# CECILIA_00.net
KiCad netlist of a schematic drawn in Altium Designer
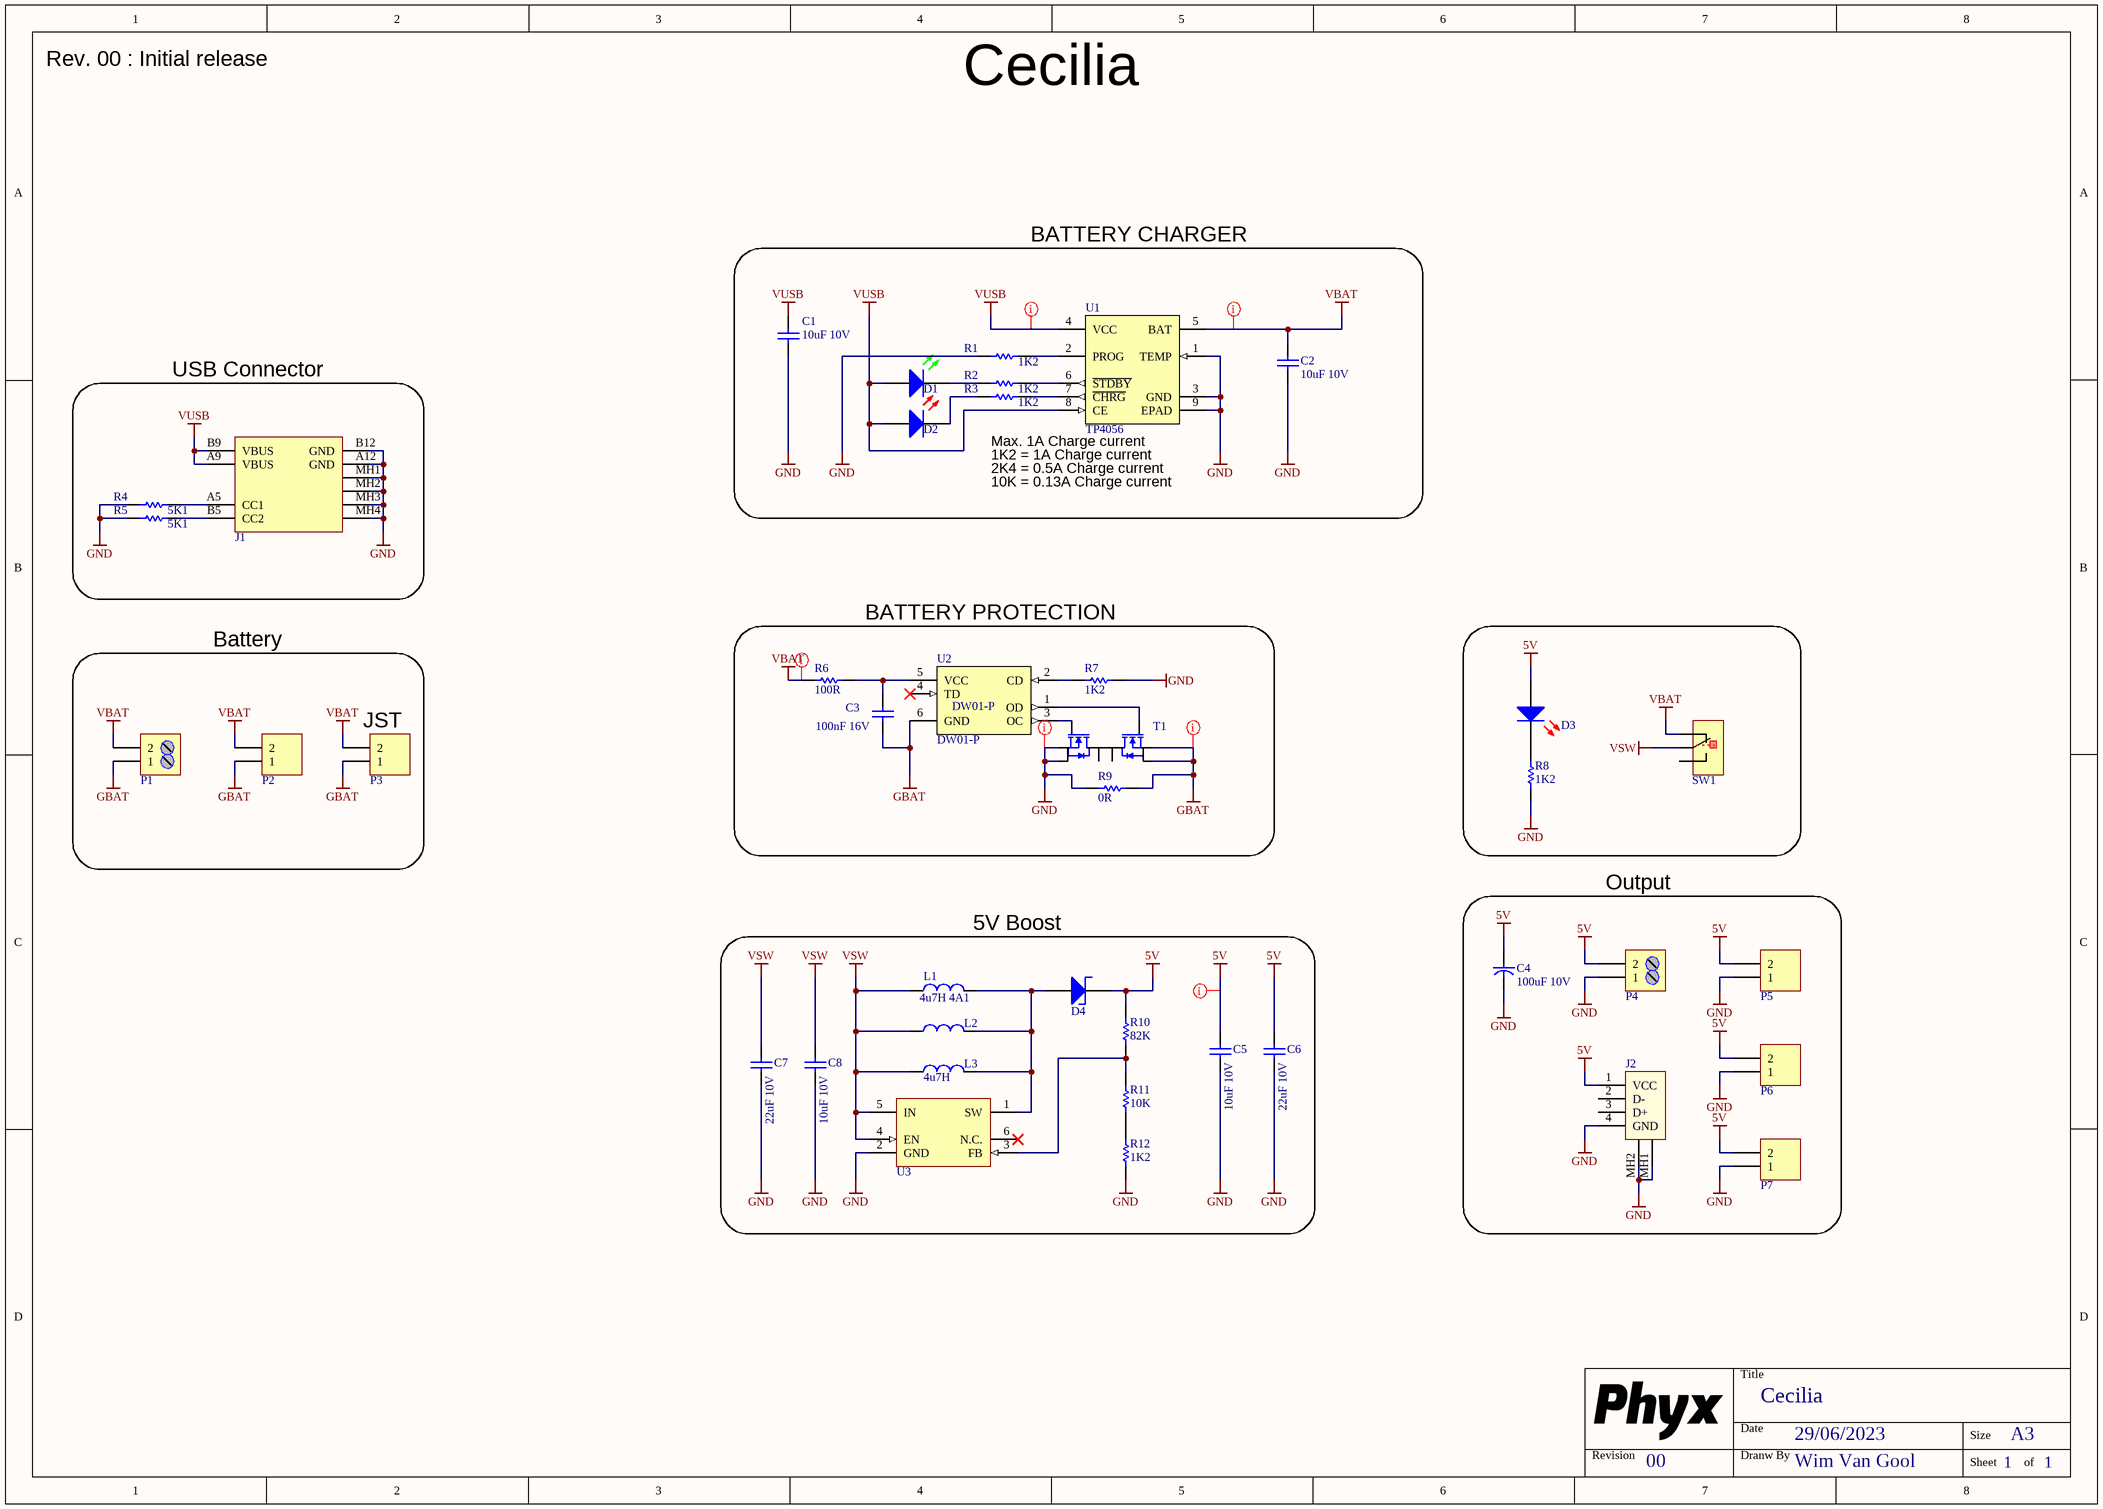
[diagram p0: CECILIA_00.SchDoc]

(export (version "E")
  (design (tool "Eeschema 10.0.6"))
  (components
    (comp (ref "C1")
      (value "10uF 10V")
      (footprint "C0805_N")
      (description "Capacitor Ceramic")
      (fields (field (name "Comment") "CAP_CERAMIC"))
      (libsource (lib "Phyx_Components") (part "CAP_CERAMIC"))
    )
    (comp (ref "C2")
      (value "10uF 10V")
      (footprint "C0805_N")
      (description "Capacitor Ceramic")
      (fields (field (name "Comment") "CAP_CERAMIC"))
      (libsource (lib "Phyx_Components") (part "CAP_CERAMIC"))
    )
    (comp (ref "C3")
      (value "100nF 16V")
      (footprint "C0603_N")
      (description "Capacitor Ceramic")
      (libsource (lib "Phyx_Components") (part "CAP_CERAMIC"))
    )
    (comp (ref "C4")
      (value "100uF 10V")
      (footprint "C_5x11_2mm")
      (description "Capacitor electrolyt")
      (fields (field (name "Comment") "CAP_POL"))
      (libsource (lib "Phyx_Components") (part "CAP_POL"))
    )
    (comp (ref "C5")
      (value "10uF 10V")
      (footprint "C0805_N")
      (description "Capacitor Ceramic")
      (fields (field (name "Comment") "CAP_CERAMIC"))
      (libsource (lib "Phyx_Components") (part "CAP_CERAMIC"))
    )
    (comp (ref "C6")
      (value "22uF 10V")
      (footprint "C1210_N")
      (description "Capacitor Ceramic")
      (fields (field (name "Comment") "CAP_CERAMIC"))
      (libsource (lib "Phyx_Components") (part "CAP_CERAMIC"))
    )
    (comp (ref "C7")
      (value "22uF 10V")
      (footprint "C1210_N")
      (description "Capacitor Ceramic")
      (fields (field (name "Comment") "CAP_CERAMIC"))
      (libsource (lib "Phyx_Components") (part "CAP_CERAMIC"))
    )
    (comp (ref "C8")
      (value "10uF 10V")
      (footprint "C0805_N")
      (description "Capacitor Ceramic")
      (fields (field (name "Comment") "CAP_CERAMIC"))
      (libsource (lib "Phyx_Components") (part "CAP_CERAMIC"))
    )
    (comp (ref "D1")
      (value "Default 0805 Green LED")
      (footprint "LED_0805_GR")
      (description "=Description")
      (libsource (lib "Phyx_Components") (part "LED_GREEN"))
    )
    (comp (ref "D2")
      (value "Default 0805 Red LED")
      (footprint "LED_0805_RD")
      (description "=Description")
      (libsource (lib "Phyx_Components") (part "LED_RED"))
    )
    (comp (ref "D3")
      (value "Default 0805 Red LED")
      (footprint "LED_0805_RD")
      (description "=Description")
      (libsource (lib "Phyx_Components") (part "LED_RED"))
    )
    (comp (ref "D4")
      (value "TSS83L45 MWG Schottky ULTRAFAST, 3A, 45V")
      (footprint "TS_SOD128")
      (description "=Description")
      (libsource (lib "Phyx_Components") (part "Schottky_21"))
    )
    (comp (ref "J1")
      (value "USB PWR C Reversible Receptacle Horizontal")
      (footprint "XKB_U262-061N-4BVC10")
      (libsource (lib "Phyx_Components") (part "USB_C_6_4"))
    )
    (comp (ref "J2")
      (value "USB type A Short horizontal connector")
      (footprint "WE_614104150121")
      (libsource (lib "Phyx_Components") (part "USB_A"))
    )
    (comp (ref "L1")
      (value "4u7H 4A1")
      (footprint "TAI_NRS8040")
      (fields (field (name "Comment") "NRS8040T4R7NJGJ"))
      (libsource (lib "Phyx_Components") (part "INDUCTOR"))
    )
    (comp (ref "L2")
      (value "VLC6045T-3R3N")
      (footprint "IND_6045")
      (libsource (lib "Phyx_Components") (part "INDUCTOR"))
    )
    (comp (ref "L3")
      (value "4u7H")
      (footprint "SNL_SWPA4020")
      (fields (field (name "Comment") "SWPA4020S4R7MT"))
      (libsource (lib "Phyx_Components") (part "INDUCTOR"))
    )
    (comp (ref "P1")
      (value "2 Way Screw HDR 5,08mm")
      (footprint "TERM_BLK-0508-2-90")
      (libsource (lib "Phyx_Components") (part "TERM_BLCK_2"))
    )
    (comp (ref "P2")
      (value "Header 2")
      (footprint "HDR1X2")
      (libsource (lib "Phyx_Components") (part "Header 2"))
    )
    (comp (ref "P3")
      (value "Header RA 1.5mm Shrouded S2B-ZR-SM4A-TF")
      (footprint "JST_ZH_S2B-ZR-SM4A-TF")
      (libsource (lib "Phyx_Components") (part "Header 2"))
    )
    (comp (ref "P4")
      (value "2 Way Screw HDR 5,08mm")
      (footprint "TERM_BLK-0508-2-90")
      (libsource (lib "Phyx_Components") (part "TERM_BLCK_2"))
    )
    (comp (ref "P5")
      (value "Header 2")
      (footprint "HDR1X2")
      (libsource (lib "Phyx_Components") (part "Header 2"))
    )
    (comp (ref "P6")
      (value "Header 2")
      (footprint "HDR1X2")
      (libsource (lib "Phyx_Components") (part "Header 2"))
    )
    (comp (ref "P7")
      (value "Header 2")
      (footprint "HDR1X2")
      (libsource (lib "Phyx_Components") (part "Header 2"))
    )
    (comp (ref "R1")
      (value "1K2")
      (footprint "R0603_N")
      (fields (field (name "Comment") "RESISTOR"))
      (libsource (lib "Phyx_Components") (part "RESISTOR"))
    )
    (comp (ref "R2")
      (value "1K2")
      (footprint "R0603_N")
      (fields (field (name "Comment") "RESISTOR"))
      (libsource (lib "Phyx_Components") (part "RESISTOR"))
    )
    (comp (ref "R3")
      (value "1K2")
      (footprint "R0603_N")
      (fields (field (name "Comment") "RESISTOR"))
      (libsource (lib "Phyx_Components") (part "RESISTOR"))
    )
    (comp (ref "R4")
      (value "5K1")
      (footprint "R0603_N")
      (fields (field (name "Comment") "RESISTOR"))
      (libsource (lib "Phyx_Components") (part "RESISTOR"))
    )
    (comp (ref "R5")
      (value "5K1")
      (footprint "R0603_N")
      (fields (field (name "Comment") "RESISTOR"))
      (libsource (lib "Phyx_Components") (part "RESISTOR"))
    )
    (comp (ref "R6")
      (value "100R")
      (footprint "R0603_N")
      (fields (field (name "Comment") "RESISTOR"))
      (libsource (lib "Phyx_Components") (part "RESISTOR"))
    )
    (comp (ref "R7")
      (value "1K2")
      (footprint "R0603_N")
      (fields (field (name "Comment") "RESISTOR"))
      (libsource (lib "Phyx_Components") (part "RESISTOR"))
    )
    (comp (ref "R8")
      (value "1K2")
      (footprint "R0603_N")
      (fields (field (name "Comment") "RESISTOR"))
      (libsource (lib "Phyx_Components") (part "RESISTOR"))
    )
    (comp (ref "R9")
      (value "0R")
      (footprint "R1206")
      (fields (field (name "Comment") "RESISTOR"))
      (libsource (lib "Phyx_Components") (part "RESISTOR"))
    )
    (comp (ref "R10")
      (value "82K")
      (footprint "R0603_N")
      (fields (field (name "Comment") "RESISTOR"))
      (libsource (lib "Phyx_Components") (part "RESISTOR"))
    )
    (comp (ref "R11")
      (value "10K")
      (footprint "R0603_N")
      (fields (field (name "Comment") "RESISTOR"))
      (libsource (lib "Phyx_Components") (part "RESISTOR"))
    )
    (comp (ref "R12")
      (value "1K2")
      (footprint "R0603_N")
      (fields (field (name "Comment") "RESISTOR"))
      (libsource (lib "Phyx_Components") (part "RESISTOR"))
    )
    (comp (ref "SW1")
      (value "mini Switch 1 pole double throw right angle")
      (footprint "SK-12D07")
      (libsource (lib "Phyx_Components") (part "SW_1P2T"))
    )
    (comp (ref "T1")
      (value "Dual N-Ch MOSFET Common Drain")
      (footprint "TSSOP_8_65P")
      (description "=Description")
      (libsource (lib "Phyx_Components") (part "N_MOSFET_FS8205A"))
    )
    (comp (ref "U1")
      (value "TP4056")
      (footprint "SOIC_N_8_TH")
      (description "=Description")
      (fields (field (name "Comment") "Single Cell LiIon charger max 1A"))
      (libsource (lib "Phyx_Components") (part "TP4056"))
    )
    (comp (ref "U2")
      (value "DW01-P")
      (footprint "SOT23-6")
      (description "=Description")
      (fields (field (name "Comment") "DW01-P single cell lithium protection"))
      (libsource (lib "Phyx_Components") (part "DW01-P"))
    )
    (comp (ref "U3")
      (value "High Efficiency 1.2MHz 2A Step Up Converter  SX1308")
      (footprint "SOT23-6")
      (description "=Description")
      (libsource (lib "Phyx_Components") (part "SX1308_Boost"))
    )
  )
  (nets
    (net (code "1") (name "5V") (class "Default")
      (node (ref "C4") (pin "1") (pinfunction "1_1") (pintype "passive"))
      (node (ref "C5") (pin "1") (pinfunction "1_1") (pintype "passive"))
      (node (ref "C6") (pin "1") (pinfunction "1_1") (pintype "passive"))
      (node (ref "D3") (pin "1") (pinfunction "A_1") (pintype "passive"))
      (node (ref "D4") (pin "1") (pinfunction "C_1") (pintype "passive"))
      (node (ref "J2") (pin "1") (pinfunction "VCC_1") (pintype "passive"))
      (node (ref "P4") (pin "2") (pinfunction "2_2") (pintype "passive"))
      (node (ref "P5") (pin "2") (pinfunction "2_2") (pintype "passive"))
      (node (ref "P6") (pin "2") (pinfunction "2_2") (pintype "passive"))
      (node (ref "P7") (pin "2") (pinfunction "2_2") (pintype "passive"))
      (node (ref "R10") (pin "1") (pinfunction "1_1") (pintype "passive"))
    )
    (net (code "2") (name "GBAT") (class "Default")
      (node (ref "C3") (pin "2") (pinfunction "2_2") (pintype "passive"))
      (node (ref "P1") (pin "1") (pinfunction "1_1") (pintype "passive"))
      (node (ref "P2") (pin "1") (pinfunction "1_1") (pintype "passive"))
      (node (ref "P3") (pin "1") (pinfunction "1_1") (pintype "passive"))
      (node (ref "R9") (pin "1") (pinfunction "1_1") (pintype "passive"))
      (node (ref "T1") (pin "2") (pinfunction "S1_2") (pintype "passive"))
      (node (ref "T1") (pin "3") (pinfunction "S1_3") (pintype "passive"))
      (node (ref "U2") (pin "6") (pinfunction "GND_6") (pintype "power_in"))
    )
    (net (code "3") (name "GND") (class "Default")
      (node (ref "C1") (pin "2") (pinfunction "2_2") (pintype "passive"))
      (node (ref "C2") (pin "2") (pinfunction "2_2") (pintype "passive"))
      (node (ref "C4") (pin "2") (pinfunction "2_2") (pintype "passive"))
      (node (ref "C5") (pin "2") (pinfunction "2_2") (pintype "passive"))
      (node (ref "C6") (pin "2") (pinfunction "2_2") (pintype "passive"))
      (node (ref "C7") (pin "2") (pinfunction "2_2") (pintype "passive"))
      (node (ref "C8") (pin "2") (pinfunction "2_2") (pintype "passive"))
      (node (ref "J1") (pin "A12") (pinfunction "GND_A12") (pintype "passive"))
      (node (ref "J1") (pin "B12") (pinfunction "GND_B12") (pintype "passive"))
      (node (ref "J1") (pin "MH1") (pinfunction "Tab_MH1") (pintype "passive"))
      (node (ref "J1") (pin "MH2") (pinfunction "Tab_MH2") (pintype "passive"))
      (node (ref "J1") (pin "MH3") (pinfunction "Tab_MH3") (pintype "passive"))
      (node (ref "J1") (pin "MH4") (pinfunction "Tab_MH4") (pintype "passive"))
      (node (ref "J2") (pin "4") (pinfunction "GND_4") (pintype "passive"))
      (node (ref "J2") (pin "MH1") (pinfunction "Tab_MH1") (pintype "passive"))
      (node (ref "J2") (pin "MH2") (pinfunction "Tab_MH2") (pintype "passive"))
      (node (ref "P4") (pin "1") (pinfunction "1_1") (pintype "passive"))
      (node (ref "P5") (pin "1") (pinfunction "1_1") (pintype "passive"))
      (node (ref "P6") (pin "1") (pinfunction "1_1") (pintype "passive"))
      (node (ref "P7") (pin "1") (pinfunction "1_1") (pintype "passive"))
      (node (ref "R1") (pin "2") (pinfunction "2_2") (pintype "passive"))
      (node (ref "R12") (pin "2") (pinfunction "2_2") (pintype "passive"))
      (node (ref "R4") (pin "2") (pinfunction "2_2") (pintype "passive"))
      (node (ref "R5") (pin "2") (pinfunction "2_2") (pintype "passive"))
      (node (ref "R7") (pin "2") (pinfunction "2_2") (pintype "passive"))
      (node (ref "R8") (pin "2") (pinfunction "2_2") (pintype "passive"))
      (node (ref "R9") (pin "2") (pinfunction "2_2") (pintype "passive"))
      (node (ref "T1") (pin "6") (pinfunction "S2_6") (pintype "passive"))
      (node (ref "T1") (pin "7") (pinfunction "S2_7") (pintype "passive"))
      (node (ref "U1") (pin "1") (pinfunction "TEMP_1") (pintype "input"))
      (node (ref "U1") (pin "3") (pinfunction "GND_3") (pintype "power_in"))
      (node (ref "U1") (pin "9") (pinfunction "EPAD_9") (pintype "power_in"))
      (node (ref "U3") (pin "2") (pinfunction "GND_2") (pintype "power_in"))
    )
    (net (code "4") (name "Net-(D1-K)") (class "Default")
      (node (ref "D1") (pin "2") (pinfunction "K_2") (pintype "passive"))
      (node (ref "R2") (pin "1") (pinfunction "1_1") (pintype "passive"))
    )
    (net (code "5") (name "Net-(D2-K)") (class "Default")
      (node (ref "D2") (pin "2") (pinfunction "K_2") (pintype "passive"))
      (node (ref "R3") (pin "1") (pinfunction "1_1") (pintype "passive"))
    )
    (net (code "6") (name "Net-(D3-K)") (class "Default")
      (node (ref "D3") (pin "2") (pinfunction "K_2") (pintype "passive"))
      (node (ref "R8") (pin "1") (pinfunction "1_1") (pintype "passive"))
    )
    (net (code "7") (name "Net-(D4-A)") (class "Default")
      (node (ref "D4") (pin "2") (pinfunction "A_2") (pintype "passive"))
      (node (ref "L1") (pin "2") (pinfunction "2_2") (pintype "passive"))
      (node (ref "L2") (pin "2") (pinfunction "2_2") (pintype "passive"))
      (node (ref "L3") (pin "2") (pinfunction "2_2") (pintype "passive"))
      (node (ref "U3") (pin "1") (pinfunction "SW_1") (pintype "power_in"))
    )
    (net (code "8") (name "Net-(J1-CC1)") (class "Default")
      (node (ref "J1") (pin "A5") (pinfunction "CC1_A5") (pintype "passive"))
      (node (ref "R4") (pin "1") (pinfunction "1_1") (pintype "passive"))
    )
    (net (code "9") (name "Net-(J1-CC2)") (class "Default")
      (node (ref "J1") (pin "B5") (pinfunction "CC2_B5") (pintype "passive"))
      (node (ref "R5") (pin "1") (pinfunction "1_1") (pintype "passive"))
    )
    (net (code "10") (name "Net-(R11-Pad2)") (class "Default")
      (node (ref "R11") (pin "2") (pinfunction "2_2") (pintype "passive"))
      (node (ref "R12") (pin "1") (pinfunction "1_1") (pintype "passive"))
    )
    (net (code "11") (name "Net-(T1-G1)") (class "Default")
      (node (ref "T1") (pin "4") (pinfunction "G1_4") (pintype "passive"))
      (node (ref "U2") (pin "1") (pinfunction "OD_1") (pintype "output"))
    )
    (net (code "12") (name "Net-(T1-G2)") (class "Default")
      (node (ref "T1") (pin "5") (pinfunction "G2_5") (pintype "passive"))
      (node (ref "U2") (pin "3") (pinfunction "OC_3") (pintype "output"))
    )
    (net (code "13") (name "Net-(U1-PROG)") (class "Default")
      (node (ref "R1") (pin "1") (pinfunction "1_1") (pintype "passive"))
      (node (ref "U1") (pin "2") (pinfunction "PROG_2") (pintype "passive"))
    )
    (net (code "14") (name "Net-(U1-~{CHRG})") (class "Default")
      (node (ref "R3") (pin "2") (pinfunction "2_2") (pintype "passive"))
      (node (ref "U1") (pin "7") (pinfunction "~{CHRG}_7") (pintype "output"))
    )
    (net (code "15") (name "Net-(U1-~{STDBY})") (class "Default")
      (node (ref "R2") (pin "2") (pinfunction "2_2") (pintype "passive"))
      (node (ref "U1") (pin "6") (pinfunction "~{STDBY}_6") (pintype "output"))
    )
    (net (code "16") (name "Net-(U2-CD)") (class "Default")
      (node (ref "R7") (pin "1") (pinfunction "1_1") (pintype "passive"))
      (node (ref "U2") (pin "2") (pinfunction "CD_2") (pintype "input"))
    )
    (net (code "17") (name "Net-(U2-VCC)") (class "Default")
      (node (ref "C3") (pin "1") (pinfunction "1_1") (pintype "passive"))
      (node (ref "R6") (pin "2") (pinfunction "2_2") (pintype "passive"))
      (node (ref "U2") (pin "5") (pinfunction "VCC_5") (pintype "power_in"))
    )
    (net (code "18") (name "Net-(U3-FB)") (class "Default")
      (node (ref "R10") (pin "2") (pinfunction "2_2") (pintype "passive"))
      (node (ref "R11") (pin "1") (pinfunction "1_1") (pintype "passive"))
      (node (ref "U3") (pin "3") (pinfunction "FB_3") (pintype "input"))
    )
    (net (code "19") (name "VBAT") (class "Default")
      (node (ref "C2") (pin "1") (pinfunction "1_1") (pintype "passive"))
      (node (ref "P1") (pin "2") (pinfunction "2_2") (pintype "passive"))
      (node (ref "P2") (pin "2") (pinfunction "2_2") (pintype "passive"))
      (node (ref "P3") (pin "2") (pinfunction "2_2") (pintype "passive"))
      (node (ref "R6") (pin "1") (pinfunction "1_1") (pintype "passive"))
      (node (ref "SW1") (pin "1") (pinfunction "1_1") (pintype "passive"))
      (node (ref "U1") (pin "5") (pinfunction "BAT_5") (pintype "power_in"))
    )
    (net (code "20") (name "VSW") (class "Default")
      (node (ref "C7") (pin "1") (pinfunction "1_1") (pintype "passive"))
      (node (ref "C8") (pin "1") (pinfunction "1_1") (pintype "passive"))
      (node (ref "L1") (pin "1") (pinfunction "1_1") (pintype "passive"))
      (node (ref "L2") (pin "1") (pinfunction "1_1") (pintype "passive"))
      (node (ref "L3") (pin "1") (pinfunction "1_1") (pintype "passive"))
      (node (ref "SW1") (pin "2") (pinfunction "2_2") (pintype "passive"))
      (node (ref "U3") (pin "4") (pinfunction "EN_4") (pintype "input"))
      (node (ref "U3") (pin "5") (pinfunction "IN_5") (pintype "power_in"))
    )
    (net (code "21") (name "VUSB") (class "Default")
      (node (ref "C1") (pin "1") (pinfunction "1_1") (pintype "passive"))
      (node (ref "D1") (pin "1") (pinfunction "A_1") (pintype "passive"))
      (node (ref "D2") (pin "1") (pinfunction "A_1") (pintype "passive"))
      (node (ref "J1") (pin "A9") (pinfunction "VBUS_A9") (pintype "passive"))
      (node (ref "J1") (pin "B9") (pinfunction "VBUS_B9") (pintype "passive"))
      (node (ref "U1") (pin "4") (pinfunction "VCC_4") (pintype "power_in"))
      (node (ref "U1") (pin "8") (pinfunction "CE_8") (pintype "input"))
    )
    (net (code "22") (name "unconnected-(J2-D+-Pad3)") (class "Default")
      (node (ref "J2") (pin "3") (pinfunction "D+_3") (pintype "passive"))
    )
    (net (code "23") (name "unconnected-(J2-D--Pad2)") (class "Default")
      (node (ref "J2") (pin "2") (pinfunction "D-_2") (pintype "passive"))
    )
    (net (code "24") (name "unconnected-(SW1-Pad3)") (class "Default")
      (node (ref "SW1") (pin "3") (pinfunction "3_3") (pintype "passive"))
    )
    (net (code "25") (name "unconnected-(T1-D1-Pad1)") (class "Default")
      (node (ref "T1") (pin "1") (pinfunction "D1_1") (pintype "passive"))
    )
    (net (code "26") (name "unconnected-(T1-D2-Pad8)") (class "Default")
      (node (ref "T1") (pin "8") (pinfunction "D2_8") (pintype "passive"))
    )
    (net (code "27") (name "unconnected-(U2-TD-Pad4)") (class "Default")
      (node (ref "U2") (pin "4") (pinfunction "TD_4") (pintype "input+no_connect"))
    )
    (net (code "28") (name "unconnected-(U3-N.C.-Pad6)") (class "Default")
      (node (ref "U3") (pin "6") (pinfunction "N.C._6") (pintype "power_in+no_connect"))
    )
  )
)
